# Connectors.net
KiCad netlist of a schematic drawn in Altium Designer
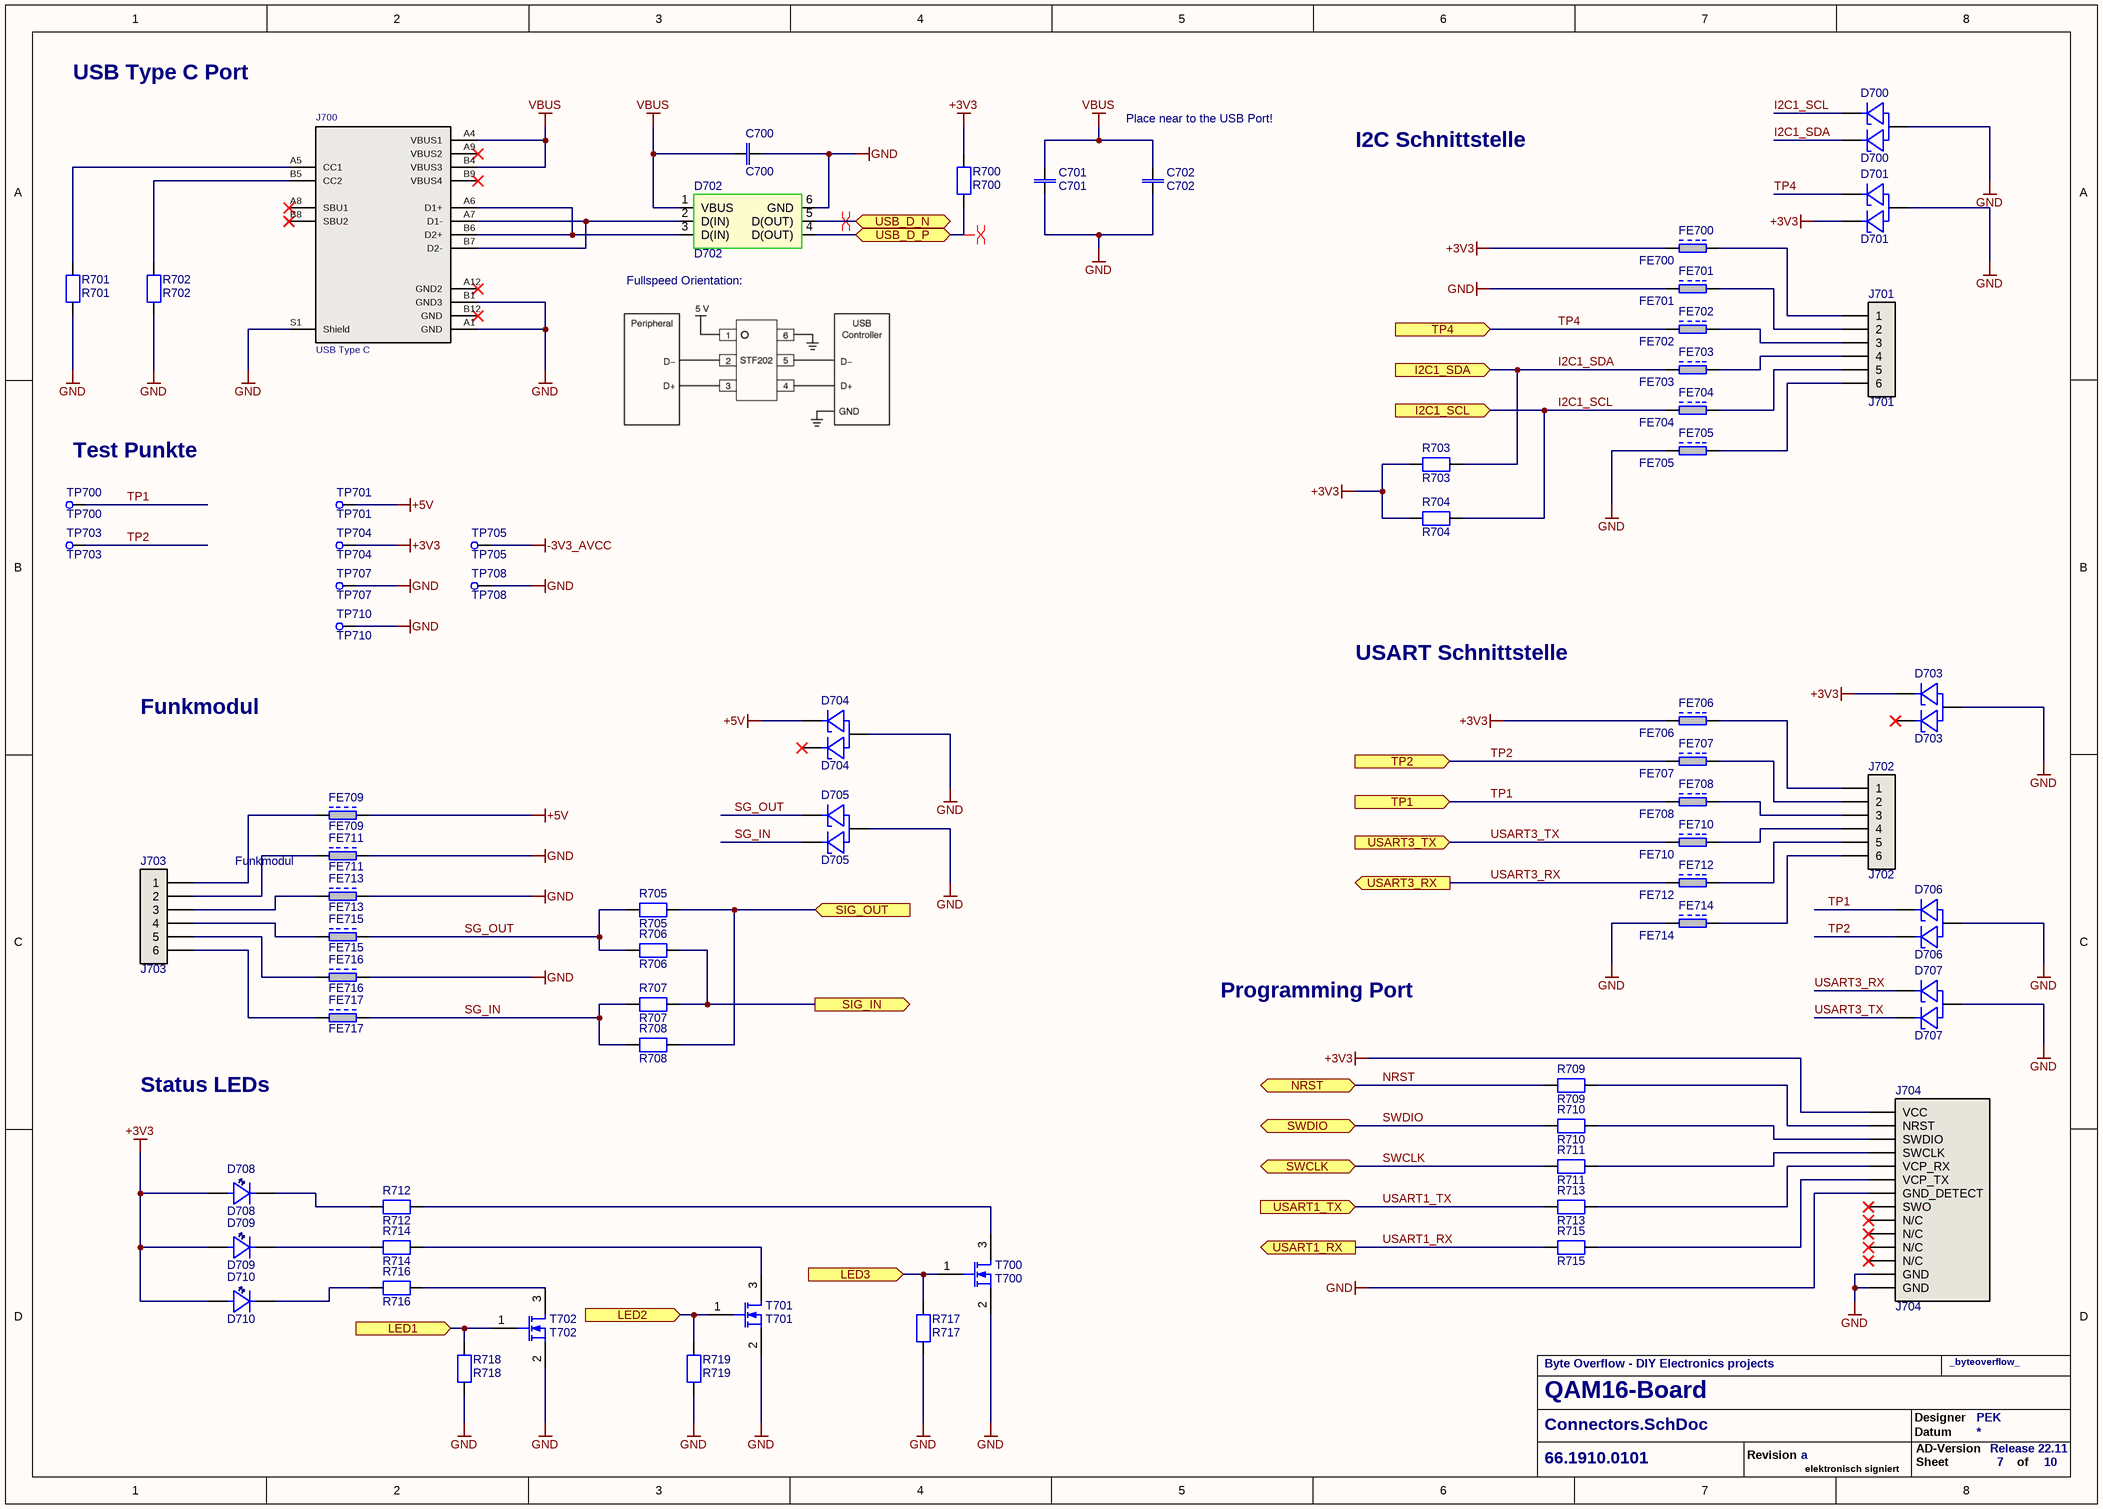
[diagram p0: Connectors.SchDoc]

(export (version "E")
  (design (tool "Eeschema 10.0.6"))
  (components
    (comp (ref "C700")
      (value "C 1uF 50V")
      (footprint "0805-2012")
      (description "Capacitor")
      (fields
        (field (name "MANUFACTURER") "Murata Electronics North America")
        (field (name "MANUFACTURER PART NUMBER") "GRM21BF51H105ZA12L")
      )
      (libsource (lib "Database_Libs1") (part "Kondensator"))
    )
    (comp (ref "C701")
      (value "C 1uF 50V")
      (footprint "0805-2012")
      (description "Capacitor")
      (fields
        (field (name "MANUFACTURER") "Murata Electronics North America")
        (field (name "MANUFACTURER PART NUMBER") "GRM21BF51H105ZA12L")
      )
      (libsource (lib "Database_Libs1") (part "Kondensator"))
    )
    (comp (ref "C702")
      (value "C 1uF 50V")
      (footprint "0805-2012")
      (description "Capacitor")
      (fields
        (field (name "MANUFACTURER") "Murata Electronics North America")
        (field (name "MANUFACTURER PART NUMBER") "GRM21BF51H105ZA12L")
      )
      (libsource (lib "Database_Libs1") (part "Kondensator"))
    )
    (comp (ref "D700")
      (value "PESD5V2S2UT 215")
      (footprint "SOT-23-3")
      (description "Diode")
      (fields
        (field (name "MANUFACTURER") "Nexperia USA Inc.")
        (field (name "MANUFACTURER PART NUMBER") "PESD5V2S2UT,215")
      )
      (libsource (lib "Database_Libs1") (part "PESD5V2S2UT"))
    )
    (comp (ref "D701")
      (value "PESD5V2S2UT 215")
      (footprint "SOT-23-3")
      (description "Diode")
      (fields
        (field (name "MANUFACTURER") "Nexperia USA Inc.")
        (field (name "MANUFACTURER PART NUMBER") "PESD5V2S2UT,215")
      )
      (libsource (lib "Database_Libs1") (part "PESD5V2S2UT"))
    )
    (comp (ref "D702")
      (value "STF202-22T1G")
      (footprint "SOT-23-6")
      (description "Diode")
      (fields (field (name "MANUFACTURER") "ON Semiconductor"))
      (libsource (lib "Database_Libs1") (part "STF202-22T1G"))
    )
    (comp (ref "D703")
      (value "PESD5V2S2UT 215")
      (footprint "SOT-23-3")
      (description "Diode")
      (fields
        (field (name "MANUFACTURER") "Nexperia USA Inc.")
        (field (name "MANUFACTURER PART NUMBER") "PESD5V2S2UT,215")
      )
      (libsource (lib "Database_Libs1") (part "PESD5V2S2UT"))
    )
    (comp (ref "D704")
      (value "PESD5V2S2UT 215")
      (footprint "SOT-23-3")
      (description "Diode")
      (fields
        (field (name "MANUFACTURER") "Nexperia USA Inc.")
        (field (name "MANUFACTURER PART NUMBER") "PESD5V2S2UT,215")
      )
      (libsource (lib "Database_Libs1") (part "PESD5V2S2UT"))
    )
    (comp (ref "D705")
      (value "PESD5V2S2UT 215")
      (footprint "SOT-23-3")
      (description "Diode")
      (fields
        (field (name "MANUFACTURER") "Nexperia USA Inc.")
        (field (name "MANUFACTURER PART NUMBER") "PESD5V2S2UT,215")
      )
      (libsource (lib "Database_Libs1") (part "PESD5V2S2UT"))
    )
    (comp (ref "D706")
      (value "PESD5V2S2UT 215")
      (footprint "SOT-23-3")
      (description "Diode")
      (fields
        (field (name "MANUFACTURER") "Nexperia USA Inc.")
        (field (name "MANUFACTURER PART NUMBER") "PESD5V2S2UT,215")
      )
      (libsource (lib "Database_Libs1") (part "PESD5V2S2UT"))
    )
    (comp (ref "D707")
      (value "PESD5V2S2UT 215")
      (footprint "SOT-23-3")
      (description "Diode")
      (fields
        (field (name "MANUFACTURER") "Nexperia USA Inc.")
        (field (name "MANUFACTURER PART NUMBER") "PESD5V2S2UT,215")
      )
      (libsource (lib "Database_Libs1") (part "PESD5V2S2UT"))
    )
    (comp (ref "D708")
      (value "LED SMD 0805")
      (footprint "0805_LED")
      (description "LED")
      (fields
        (field (name "MANUFACTURER") "Dialight")
        (field (name "MANUFACTURER PART NUMBER") "5988170107F")
        (field (name "VERIFICATION") "25.01.2013 MLP")
      )
      (libsource (lib "Database_Libs1") (part "LED"))
    )
    (comp (ref "D709")
      (value "LED SMD 0805")
      (footprint "0805_LED")
      (description "LED")
      (fields
        (field (name "MANUFACTURER") "Dialight")
        (field (name "MANUFACTURER PART NUMBER") "5988170107F")
        (field (name "VERIFICATION") "25.01.2013 MLP")
      )
      (libsource (lib "Database_Libs1") (part "LED"))
    )
    (comp (ref "D710")
      (value "LED SMD 0805")
      (footprint "0805_LED")
      (description "LED")
      (fields
        (field (name "MANUFACTURER") "Dialight")
        (field (name "MANUFACTURER PART NUMBER") "5988170107F")
        (field (name "VERIFICATION") "25.01.2013 MLP")
      )
      (libsource (lib "Database_Libs1") (part "LED"))
    )
    (comp (ref "FE700")
      (value "BLM18AG102SN1D")
      (footprint "0603-1608")
      (description "Ferrite")
      (fields (field (name "MANUFACTURER") "Murata Electronics North America"))
      (libsource (lib "Database_Libs1") (part "Ferrit"))
    )
    (comp (ref "FE701")
      (value "BLM18AG102SN1D")
      (footprint "0603-1608")
      (description "Ferrite")
      (fields (field (name "MANUFACTURER") "Murata Electronics North America"))
      (libsource (lib "Database_Libs1") (part "Ferrit"))
    )
    (comp (ref "FE702")
      (value "BLM18AG102SN1D")
      (footprint "0603-1608")
      (description "Ferrite")
      (fields (field (name "MANUFACTURER") "Murata Electronics North America"))
      (libsource (lib "Database_Libs1") (part "Ferrit"))
    )
    (comp (ref "FE703")
      (value "BLM18AG102SN1D")
      (footprint "0603-1608")
      (description "Ferrite")
      (fields (field (name "MANUFACTURER") "Murata Electronics North America"))
      (libsource (lib "Database_Libs1") (part "Ferrit"))
    )
    (comp (ref "FE704")
      (value "BLM18AG102SN1D")
      (footprint "0603-1608")
      (description "Ferrite")
      (fields (field (name "MANUFACTURER") "Murata Electronics North America"))
      (libsource (lib "Database_Libs1") (part "Ferrit"))
    )
    (comp (ref "FE705")
      (value "BLM18AG102SN1D")
      (footprint "0603-1608")
      (description "Ferrite")
      (fields (field (name "MANUFACTURER") "Murata Electronics North America"))
      (libsource (lib "Database_Libs1") (part "Ferrit"))
    )
    (comp (ref "FE706")
      (value "BLM18AG102SN1D")
      (footprint "0603-1608")
      (description "Ferrite")
      (fields (field (name "MANUFACTURER") "Murata Electronics North America"))
      (libsource (lib "Database_Libs1") (part "Ferrit"))
    )
    (comp (ref "FE707")
      (value "BLM18AG102SN1D")
      (footprint "0603-1608")
      (description "Ferrite")
      (fields (field (name "MANUFACTURER") "Murata Electronics North America"))
      (libsource (lib "Database_Libs1") (part "Ferrit"))
    )
    (comp (ref "FE708")
      (value "BLM18AG102SN1D")
      (footprint "0603-1608")
      (description "Ferrite")
      (fields (field (name "MANUFACTURER") "Murata Electronics North America"))
      (libsource (lib "Database_Libs1") (part "Ferrit"))
    )
    (comp (ref "FE709")
      (value "BLM18AG102SN1D")
      (footprint "0603-1608")
      (description "Ferrite")
      (fields (field (name "MANUFACTURER") "Murata Electronics North America"))
      (libsource (lib "Database_Libs1") (part "Ferrit"))
    )
    (comp (ref "FE710")
      (value "BLM18AG102SN1D")
      (footprint "0603-1608")
      (description "Ferrite")
      (fields (field (name "MANUFACTURER") "Murata Electronics North America"))
      (libsource (lib "Database_Libs1") (part "Ferrit"))
    )
    (comp (ref "FE711")
      (value "BLM18AG102SN1D")
      (footprint "0603-1608")
      (description "Ferrite")
      (fields (field (name "MANUFACTURER") "Murata Electronics North America"))
      (libsource (lib "Database_Libs1") (part "Ferrit"))
    )
    (comp (ref "FE712")
      (value "BLM18AG102SN1D")
      (footprint "0603-1608")
      (description "Ferrite")
      (fields (field (name "MANUFACTURER") "Murata Electronics North America"))
      (libsource (lib "Database_Libs1") (part "Ferrit"))
    )
    (comp (ref "FE713")
      (value "BLM18AG102SN1D")
      (footprint "0603-1608")
      (description "Ferrite")
      (fields (field (name "MANUFACTURER") "Murata Electronics North America"))
      (libsource (lib "Database_Libs1") (part "Ferrit"))
    )
    (comp (ref "FE714")
      (value "BLM18AG102SN1D")
      (footprint "0603-1608")
      (description "Ferrite")
      (fields (field (name "MANUFACTURER") "Murata Electronics North America"))
      (libsource (lib "Database_Libs1") (part "Ferrit"))
    )
    (comp (ref "FE715")
      (value "BLM18AG102SN1D")
      (footprint "0603-1608")
      (description "Ferrite")
      (fields (field (name "MANUFACTURER") "Murata Electronics North America"))
      (libsource (lib "Database_Libs1") (part "Ferrit"))
    )
    (comp (ref "FE716")
      (value "BLM18AG102SN1D")
      (footprint "0603-1608")
      (description "Ferrite")
      (fields (field (name "MANUFACTURER") "Murata Electronics North America"))
      (libsource (lib "Database_Libs1") (part "Ferrit"))
    )
    (comp (ref "FE717")
      (value "BLM18AG102SN1D")
      (footprint "0603-1608")
      (description "Ferrite")
      (fields (field (name "MANUFACTURER") "Murata Electronics North America"))
      (libsource (lib "Database_Libs1") (part "Ferrit"))
    )
    (comp (ref "J700")
      (value "USB Type C")
      (footprint "GCT_USB4105")
      (description "Connector")
      (fields (field (name "MP") "1054500101") (field (name "MF") "Molex"))
      (libsource (lib "Database_Libs1") (part "USB 2.0 Type C"))
    )
    (comp (ref "J701")
      (value "Stiftleiste 6pol")
      (footprint "Stiftleiste_6pol")
      (description "Connector")
      (libsource (lib "Database_Libs1") (part "Stiftleiste_6pol"))
    )
    (comp (ref "J702")
      (value "Stiftleiste 6pol")
      (footprint "Stiftleiste_6pol")
      (description "Connector")
      (libsource (lib "Database_Libs1") (part "Stiftleiste_6pol"))
    )
    (comp (ref "J703")
      (value "Stiftleiste 6pol")
      (footprint "Stiftleiste_6pol")
      (description "Connector")
      (libsource (lib "") (part "Stiftleiste_6pol_1"))
    )
    (comp (ref "J704")
      (value "Stiftleiste_Stlink_V3")
      (footprint "SAMTEC_FTSH-107-01-L-DV-K-A")
      (description "Connector")
      (fields
        (field (name "MANUFACTURER") "Samtec")
        (field (name "MANUFACTURER PART NUMBER") "FTSH-107-01-L-DV-K-A")
      )
      (libsource (lib "Database_Libs1") (part "Stiftleiste_Stlink_V3"))
    )
    (comp (ref "R700")
      (value "R 1.5k 1%")
      (footprint "0603-1608")
      (description "Resistor")
      (fields
        (field (name "MANUFACTURER") "Vishay Dale")
        (field (name "MANUFACTURER PART NUMBER") "CRCW06031K50FKEA")
        (field (name "VERIFICATION") "05.07.2012 OPT")
      )
      (libsource (lib "Database_Libs1") (part "Resistor"))
    )
    (comp (ref "R701")
      (value "R 5.1k 1%")
      (footprint "0603-1608")
      (description "Resistor")
      (fields
        (field (name "MANUFACTURER") "Vishay Dale")
        (field (name "MANUFACTURER PART NUMBER") "CRCW06035K10FKEA")
        (field (name "VERIFICATION") "05.07.2012 OPT")
      )
      (libsource (lib "Database_Libs1") (part "Resistor"))
    )
    (comp (ref "R702")
      (value "R 5.1k 1%")
      (footprint "0603-1608")
      (description "Resistor")
      (fields
        (field (name "MANUFACTURER") "Vishay Dale")
        (field (name "MANUFACTURER PART NUMBER") "CRCW06035K10FKEA")
        (field (name "VERIFICATION") "05.07.2012 OPT")
      )
      (libsource (lib "Database_Libs1") (part "Resistor"))
    )
    (comp (ref "R703")
      (value "R 2.2k 1%")
      (footprint "0603-1608")
      (description "Resistor")
      (fields
        (field (name "MANUFACTURER") "Vishay Dale")
        (field (name "MANUFACTURER PART NUMBER") "CRCW06032K20FKEA")
        (field (name "VERIFICATION") "05.07.2012 OPT")
      )
      (libsource (lib "Database_Libs1") (part "Resistor"))
    )
    (comp (ref "R704")
      (value "R 2.2k 1%")
      (footprint "0603-1608")
      (description "Resistor")
      (fields
        (field (name "MANUFACTURER") "Vishay Dale")
        (field (name "MANUFACTURER PART NUMBER") "CRCW06032K20FKEA")
        (field (name "VERIFICATION") "05.07.2012 OPT")
      )
      (libsource (lib "Database_Libs1") (part "Resistor"))
    )
    (comp (ref "R705")
      (value "R 0E 1%")
      (footprint "0805-2012")
      (description "Resistor")
      (fields
        (field (name "MANUFACTURER") "Vishay Dale")
        (field (name "MANUFACTURER PART NUMBER") "CRCW08050000Z0EAHP")
        (field (name "VERIFICATION") "05.03.2013 ENP")
      )
      (libsource (lib "Database_Libs1") (part "Resistor"))
    )
    (comp (ref "R706")
      (value "R 0E 1%")
      (footprint "0805-2012")
      (description "Resistor")
      (fields
        (field (name "MANUFACTURER") "Vishay Dale")
        (field (name "MANUFACTURER PART NUMBER") "CRCW08050000Z0EAHP")
        (field (name "VERIFICATION") "05.03.2013 ENP")
      )
      (libsource (lib "Database_Libs1") (part "Resistor"))
    )
    (comp (ref "R707")
      (value "R 0E 1%")
      (footprint "0805-2012")
      (description "Resistor")
      (fields
        (field (name "MANUFACTURER") "Vishay Dale")
        (field (name "MANUFACTURER PART NUMBER") "CRCW08050000Z0EAHP")
        (field (name "VERIFICATION") "05.03.2013 ENP")
      )
      (libsource (lib "Database_Libs1") (part "Resistor"))
    )
    (comp (ref "R708")
      (value "R 0E 1%")
      (footprint "0805-2012")
      (description "Resistor")
      (fields
        (field (name "MANUFACTURER") "Vishay Dale")
        (field (name "MANUFACTURER PART NUMBER") "CRCW08050000Z0EAHP")
        (field (name "VERIFICATION") "05.03.2013 ENP")
      )
      (libsource (lib "Database_Libs1") (part "Resistor"))
    )
    (comp (ref "R709")
      (value "R 100E 1%")
      (footprint "0603-1608")
      (description "Resistor")
      (fields
        (field (name "MANUFACTURER") "Vishay Dale")
        (field (name "MANUFACTURER PART NUMBER") "CRCW0603100RFKEA")
        (field (name "VERIFICATION") "05.07.2012 OPT")
      )
      (libsource (lib "Database_Libs1") (part "Resistor"))
    )
    (comp (ref "R710")
      (value "R 100E 1%")
      (footprint "0603-1608")
      (description "Resistor")
      (fields
        (field (name "MANUFACTURER") "Vishay Dale")
        (field (name "MANUFACTURER PART NUMBER") "CRCW0603100RFKEA")
        (field (name "VERIFICATION") "05.07.2012 OPT")
      )
      (libsource (lib "Database_Libs1") (part "Resistor"))
    )
    (comp (ref "R711")
      (value "R 100E 1%")
      (footprint "0603-1608")
      (description "Resistor")
      (fields
        (field (name "MANUFACTURER") "Vishay Dale")
        (field (name "MANUFACTURER PART NUMBER") "CRCW0603100RFKEA")
        (field (name "VERIFICATION") "05.07.2012 OPT")
      )
      (libsource (lib "Database_Libs1") (part "Resistor"))
    )
    (comp (ref "R712")
      (value "R 560E 1%")
      (footprint "0805-2012")
      (description "Resistor")
      (fields
        (field (name "MANUFACTURER") "Panasonic Electronic Components")
        (field (name "MANUFACTURER PART NUMBER") "ERJ-6ENF5600V")
      )
      (libsource (lib "Database_Libs1") (part "Resistor"))
    )
    (comp (ref "R713")
      (value "R 100E 1%")
      (footprint "0603-1608")
      (description "Resistor")
      (fields
        (field (name "MANUFACTURER") "Vishay Dale")
        (field (name "MANUFACTURER PART NUMBER") "CRCW0603100RFKEA")
        (field (name "VERIFICATION") "05.07.2012 OPT")
      )
      (libsource (lib "Database_Libs1") (part "Resistor"))
    )
    (comp (ref "R714")
      (value "R 560E 1%")
      (footprint "0805-2012")
      (description "Resistor")
      (fields
        (field (name "MANUFACTURER") "Panasonic Electronic Components")
        (field (name "MANUFACTURER PART NUMBER") "ERJ-6ENF5600V")
      )
      (libsource (lib "Database_Libs1") (part "Resistor"))
    )
    (comp (ref "R715")
      (value "R 100E 1%")
      (footprint "0603-1608")
      (description "Resistor")
      (fields
        (field (name "MANUFACTURER") "Vishay Dale")
        (field (name "MANUFACTURER PART NUMBER") "CRCW0603100RFKEA")
        (field (name "VERIFICATION") "05.07.2012 OPT")
      )
      (libsource (lib "Database_Libs1") (part "Resistor"))
    )
    (comp (ref "R716")
      (value "R 560E 1%")
      (footprint "0805-2012")
      (description "Resistor")
      (fields
        (field (name "MANUFACTURER") "Panasonic Electronic Components")
        (field (name "MANUFACTURER PART NUMBER") "ERJ-6ENF5600V")
      )
      (libsource (lib "Database_Libs1") (part "Resistor"))
    )
    (comp (ref "R717")
      (value "R 100k 1%")
      (footprint "0603-1608")
      (description "Resistor")
      (fields
        (field (name "MANUFACTURER") "Vishay Dale")
        (field (name "MANUFACTURER PART NUMBER") "CRCW0603100KFKEA")
        (field (name "VERIFICATION") "05.07.2012 OPT")
      )
      (libsource (lib "Database_Libs1") (part "Resistor"))
    )
    (comp (ref "R718")
      (value "R 100k 1%")
      (footprint "0603-1608")
      (description "Resistor")
      (fields
        (field (name "MANUFACTURER") "Vishay Dale")
        (field (name "MANUFACTURER PART NUMBER") "CRCW0603100KFKEA")
        (field (name "VERIFICATION") "05.07.2012 OPT")
      )
      (libsource (lib "Database_Libs1") (part "Resistor"))
    )
    (comp (ref "R719")
      (value "R 100k 1%")
      (footprint "0603-1608")
      (description "Resistor")
      (fields
        (field (name "MANUFACTURER") "Vishay Dale")
        (field (name "MANUFACTURER PART NUMBER") "CRCW0603100KFKEA")
        (field (name "VERIFICATION") "05.07.2012 OPT")
      )
      (libsource (lib "Database_Libs1") (part "Resistor"))
    )
    (comp (ref "T700")
      (value "SI1308EDL-T1-GE3")
      (footprint "SOT-323")
      (description "FET")
      (fields (field (name "MANUFACTURER") "Vishay Siliconix"))
      (libsource (lib "Database_Libs1") (part "FDV305N"))
    )
    (comp (ref "T701")
      (value "SI1308EDL-T1-GE3")
      (footprint "SOT-323")
      (description "FET")
      (fields (field (name "MANUFACTURER") "Vishay Siliconix"))
      (libsource (lib "Database_Libs1") (part "FDV305N"))
    )
    (comp (ref "T702")
      (value "SI1308EDL-T1-GE3")
      (footprint "SOT-323")
      (description "FET")
      (fields (field (name "MANUFACTURER") "Vishay Siliconix"))
      (libsource (lib "Database_Libs1") (part "FDV305N"))
    )
    (comp (ref "TP700")
      (value "Testpoint")
      (footprint "Testpoint")
      (fields
        (field (name "MANUFACTURER") "Keystone Electronics")
        (field (name "MANUFACTURER PART NUMBER") "5006")
      )
      (libsource (lib "Database_Libs1") (part "Testpoint"))
    )
    (comp (ref "TP701")
      (value "Testpoint")
      (footprint "Testpoint")
      (fields
        (field (name "MANUFACTURER") "Keystone Electronics")
        (field (name "MANUFACTURER PART NUMBER") "5006")
      )
      (libsource (lib "Database_Libs1") (part "Testpoint"))
    )
    (comp (ref "TP703")
      (value "Testpoint")
      (footprint "Testpoint")
      (fields
        (field (name "MANUFACTURER") "Keystone Electronics")
        (field (name "MANUFACTURER PART NUMBER") "5006")
      )
      (libsource (lib "Database_Libs1") (part "Testpoint"))
    )
    (comp (ref "TP704")
      (value "Testpoint")
      (footprint "Testpoint")
      (fields
        (field (name "MANUFACTURER") "Keystone Electronics")
        (field (name "MANUFACTURER PART NUMBER") "5006")
      )
      (libsource (lib "Database_Libs1") (part "Testpoint"))
    )
    (comp (ref "TP705")
      (value "Testpoint")
      (footprint "Testpoint")
      (fields
        (field (name "MANUFACTURER") "Keystone Electronics")
        (field (name "MANUFACTURER PART NUMBER") "5006")
      )
      (libsource (lib "Database_Libs1") (part "Testpoint"))
    )
    (comp (ref "TP707")
      (value "Testpoint")
      (footprint "Testpoint")
      (fields
        (field (name "MANUFACTURER") "Keystone Electronics")
        (field (name "MANUFACTURER PART NUMBER") "5006")
      )
      (libsource (lib "Database_Libs1") (part "Testpoint"))
    )
    (comp (ref "TP708")
      (value "Testpoint")
      (footprint "Testpoint")
      (fields
        (field (name "MANUFACTURER") "Keystone Electronics")
        (field (name "MANUFACTURER PART NUMBER") "5006")
      )
      (libsource (lib "Database_Libs1") (part "Testpoint"))
    )
    (comp (ref "TP710")
      (value "Testpoint")
      (footprint "Testpoint")
      (fields
        (field (name "MANUFACTURER") "Keystone Electronics")
        (field (name "MANUFACTURER PART NUMBER") "5006")
      )
      (libsource (lib "Database_Libs1") (part "Testpoint"))
    )
  )
  (nets
    (net (code "1") (name "+3V3") (class "Default")
      (node (ref "D701") (pin "1") (pinfunction "1_1") (pintype "passive"))
      (node (ref "D703") (pin "2") (pinfunction "2_2") (pintype "passive"))
      (node (ref "D708") (pin "1") (pinfunction "A_1") (pintype "passive"))
      (node (ref "D709") (pin "1") (pinfunction "A_1") (pintype "passive"))
      (node (ref "D710") (pin "1") (pinfunction "A_1") (pintype "passive"))
      (node (ref "FE700") (pin "1") (pintype "passive"))
      (node (ref "FE706") (pin "1") (pintype "passive"))
      (node (ref "J704") (pin "3") (pinfunction "VCC_3") (pintype "passive"))
      (node (ref "R700") (pin "1") (pinfunction "1_1") (pintype "passive"))
      (node (ref "R703") (pin "1") (pinfunction "1_1") (pintype "passive"))
      (node (ref "R704") (pin "1") (pinfunction "1_1") (pintype "passive"))
      (node (ref "TP704") (pin "1") (pintype "passive"))
    )
    (net (code "2") (name "+5V") (class "Default")
      (node (ref "D704") (pin "2") (pinfunction "2_2") (pintype "passive"))
      (node (ref "FE709") (pin "1") (pintype "passive"))
      (node (ref "TP701") (pin "1") (pintype "passive"))
    )
    (net (code "3") (name "-3V3_AVCC") (class "Default") (node (ref "TP705") (pin "1") (pintype "passive")))
    (net (code "4") (name "/I2C1_SCL") (class "Default")
      (node (ref "D700") (pin "2") (pinfunction "2_2") (pintype "passive"))
      (node (ref "FE704") (pin "1") (pintype "passive"))
      (node (ref "R704") (pin "2") (pinfunction "2_2") (pintype "passive"))
    )
    (net (code "5") (name "/I2C1_SDA") (class "Default")
      (node (ref "D700") (pin "1") (pinfunction "1_1") (pintype "passive"))
      (node (ref "FE703") (pin "1") (pintype "passive"))
      (node (ref "R703") (pin "2") (pinfunction "2_2") (pintype "passive"))
    )
    (net (code "6") (name "/LED1") (class "Default")
      (node (ref "R718") (pin "1") (pinfunction "1_1") (pintype "passive"))
      (node (ref "T702") (pin "1") (pinfunction "G_1") (pintype "passive"))
    )
    (net (code "7") (name "/LED2") (class "Default")
      (node (ref "R719") (pin "1") (pinfunction "1_1") (pintype "passive"))
      (node (ref "T701") (pin "1") (pinfunction "G_1") (pintype "passive"))
    )
    (net (code "8") (name "/LED3") (class "Default")
      (node (ref "R717") (pin "1") (pinfunction "1_1") (pintype "passive"))
      (node (ref "T700") (pin "1") (pinfunction "G_1") (pintype "passive"))
    )
    (net (code "9") (name "/NRST") (class "Default")
      (node (ref "R709") (pin "1") (pinfunction "1_1") (pintype "passive"))
    )
    (net (code "10") (name "/SG_IN") (class "Default")
      (node (ref "D705") (pin "1") (pinfunction "1_1") (pintype "passive"))
      (node (ref "FE717") (pin "1") (pintype "passive"))
      (node (ref "R707") (pin "1") (pinfunction "1_1") (pintype "passive"))
      (node (ref "R708") (pin "1") (pinfunction "1_1") (pintype "passive"))
    )
    (net (code "11") (name "/SG_OUT") (class "Default")
      (node (ref "D705") (pin "2") (pinfunction "2_2") (pintype "passive"))
      (node (ref "FE715") (pin "1") (pintype "passive"))
      (node (ref "R705") (pin "1") (pinfunction "1_1") (pintype "passive"))
      (node (ref "R706") (pin "1") (pinfunction "1_1") (pintype "passive"))
    )
    (net (code "12") (name "/SIG_IN") (class "Default")
      (node (ref "R706") (pin "2") (pinfunction "2_2") (pintype "passive"))
      (node (ref "R707") (pin "2") (pinfunction "2_2") (pintype "passive"))
    )
    (net (code "13") (name "/SIG_OUT") (class "Default")
      (node (ref "R705") (pin "2") (pinfunction "2_2") (pintype "passive"))
      (node (ref "R708") (pin "2") (pinfunction "2_2") (pintype "passive"))
    )
    (net (code "14") (name "/SWCLK") (class "Default")
      (node (ref "R711") (pin "1") (pinfunction "1_1") (pintype "passive"))
    )
    (net (code "15") (name "/SWDIO") (class "Default")
      (node (ref "R710") (pin "1") (pinfunction "1_1") (pintype "passive"))
    )
    (net (code "16") (name "/TP1") (class "Default")
      (node (ref "D706") (pin "2") (pinfunction "2_2") (pintype "passive"))
      (node (ref "FE708") (pin "1") (pintype "passive"))
      (node (ref "TP700") (pin "1") (pintype "passive"))
    )
    (net (code "17") (name "/TP2") (class "Default")
      (node (ref "D706") (pin "1") (pinfunction "1_1") (pintype "passive"))
      (node (ref "FE707") (pin "1") (pintype "passive"))
      (node (ref "TP703") (pin "1") (pintype "passive"))
    )
    (net (code "18") (name "/TP4") (class "Default")
      (node (ref "D701") (pin "2") (pinfunction "2_2") (pintype "passive"))
      (node (ref "FE702") (pin "1") (pintype "passive"))
    )
    (net (code "19") (name "/USART1_RX") (class "Default")
      (node (ref "R715") (pin "1") (pinfunction "1_1") (pintype "passive"))
    )
    (net (code "20") (name "/USART1_TX") (class "Default")
      (node (ref "R713") (pin "1") (pinfunction "1_1") (pintype "passive"))
    )
    (net (code "21") (name "/USART3_RX") (class "Default")
      (node (ref "D707") (pin "2") (pinfunction "2_2") (pintype "passive"))
      (node (ref "FE712") (pin "1") (pintype "passive"))
    )
    (net (code "22") (name "/USART3_TX") (class "Default")
      (node (ref "D707") (pin "1") (pinfunction "1_1") (pintype "passive"))
      (node (ref "FE710") (pin "1") (pintype "passive"))
    )
    (net (code "23") (name "/USB_D_N") (class "Default")
      (node (ref "D702") (pin "5") (pinfunction "D(OUT)_5") (pintype "passive"))
    )
    (net (code "24") (name "/USB_D_P") (class "Default")
      (node (ref "D702") (pin "4") (pinfunction "D(OUT)_4") (pintype "passive"))
      (node (ref "R700") (pin "2") (pinfunction "2_2") (pintype "passive"))
    )
    (net (code "25") (name "GND") (class "Default")
      (node (ref "C700") (pin "2") (pinfunction "2_2") (pintype "passive"))
      (node (ref "C701") (pin "2") (pinfunction "2_2") (pintype "passive"))
      (node (ref "C702") (pin "2") (pinfunction "2_2") (pintype "passive"))
      (node (ref "D700") (pin "3") (pinfunction "3_3") (pintype "passive"))
      (node (ref "D701") (pin "3") (pinfunction "3_3") (pintype "passive"))
      (node (ref "D702") (pin "6") (pinfunction "GND_6") (pintype "passive"))
      (node (ref "D703") (pin "3") (pinfunction "3_3") (pintype "passive"))
      (node (ref "D704") (pin "3") (pinfunction "3_3") (pintype "passive"))
      (node (ref "D705") (pin "3") (pinfunction "3_3") (pintype "passive"))
      (node (ref "D706") (pin "3") (pinfunction "3_3") (pintype "passive"))
      (node (ref "D707") (pin "3") (pinfunction "3_3") (pintype "passive"))
      (node (ref "FE701") (pin "1") (pintype "passive"))
      (node (ref "FE705") (pin "1") (pintype "passive"))
      (node (ref "FE711") (pin "1") (pintype "passive"))
      (node (ref "FE713") (pin "1") (pintype "passive"))
      (node (ref "FE714") (pin "1") (pintype "passive"))
      (node (ref "FE716") (pin "1") (pintype "passive"))
      (node (ref "J700") (pin "A1") (pinfunction "GND_A1") (pintype "passive"))
      (node (ref "J700") (pin "B1") (pinfunction "GND3_B1") (pintype "passive"))
      (node (ref "J700") (pin "S1") (pinfunction "Shield_S1") (pintype "passive"))
      (node (ref "J704") (pin "11") (pinfunction "GND_DETECT_11") (pintype "passive"))
      (node (ref "J704") (pin "5") (pinfunction "GND_5") (pintype "passive"))
      (node (ref "J704") (pin "7") (pinfunction "GND_7") (pintype "passive"))
      (node (ref "R701") (pin "2") (pinfunction "2_2") (pintype "passive"))
      (node (ref "R702") (pin "2") (pinfunction "2_2") (pintype "passive"))
      (node (ref "R717") (pin "2") (pinfunction "2_2") (pintype "passive"))
      (node (ref "R718") (pin "2") (pinfunction "2_2") (pintype "passive"))
      (node (ref "R719") (pin "2") (pinfunction "2_2") (pintype "passive"))
      (node (ref "T700") (pin "2") (pinfunction "S_2") (pintype "passive"))
      (node (ref "T701") (pin "2") (pinfunction "S_2") (pintype "passive"))
      (node (ref "T702") (pin "2") (pinfunction "S_2") (pintype "passive"))
      (node (ref "TP707") (pin "1") (pintype "passive"))
      (node (ref "TP708") (pin "1") (pintype "passive"))
      (node (ref "TP710") (pin "1") (pintype "passive"))
    )
    (net (code "26") (name "Net-(D708-K)") (class "Default")
      (node (ref "D708") (pin "2") (pinfunction "K_2") (pintype "passive"))
      (node (ref "R712") (pin "1") (pinfunction "1_1") (pintype "passive"))
    )
    (net (code "27") (name "Net-(D709-K)") (class "Default")
      (node (ref "D709") (pin "2") (pinfunction "K_2") (pintype "passive"))
      (node (ref "R714") (pin "1") (pinfunction "1_1") (pintype "passive"))
    )
    (net (code "28") (name "Net-(D710-K)") (class "Default")
      (node (ref "D710") (pin "2") (pinfunction "K_2") (pintype "passive"))
      (node (ref "R716") (pin "1") (pinfunction "1_1") (pintype "passive"))
    )
    (net (code "29") (name "Net-(FE700-Pad2)") (class "Default")
      (node (ref "FE700") (pin "2") (pintype "passive"))
      (node (ref "J701") (pin "1") (pinfunction "1_1") (pintype "passive"))
    )
    (net (code "30") (name "Net-(FE701-Pad2)") (class "Default")
      (node (ref "FE701") (pin "2") (pintype "passive"))
      (node (ref "J701") (pin "2") (pinfunction "2_2") (pintype "passive"))
    )
    (net (code "31") (name "Net-(FE702-Pad2)") (class "Default")
      (node (ref "FE702") (pin "2") (pintype "passive"))
      (node (ref "J701") (pin "3") (pinfunction "3_3") (pintype "passive"))
    )
    (net (code "32") (name "Net-(FE703-Pad2)") (class "Default")
      (node (ref "FE703") (pin "2") (pintype "passive"))
      (node (ref "J701") (pin "4") (pinfunction "4_4") (pintype "passive"))
    )
    (net (code "33") (name "Net-(FE704-Pad2)") (class "Default")
      (node (ref "FE704") (pin "2") (pintype "passive"))
      (node (ref "J701") (pin "5") (pinfunction "5_5") (pintype "passive"))
    )
    (net (code "34") (name "Net-(FE705-Pad2)") (class "Default")
      (node (ref "FE705") (pin "2") (pintype "passive"))
      (node (ref "J701") (pin "6") (pinfunction "6_6") (pintype "passive"))
    )
    (net (code "35") (name "Net-(FE706-Pad2)") (class "Default")
      (node (ref "FE706") (pin "2") (pintype "passive"))
      (node (ref "J702") (pin "1") (pinfunction "1_1") (pintype "passive"))
    )
    (net (code "36") (name "Net-(FE707-Pad2)") (class "Default")
      (node (ref "FE707") (pin "2") (pintype "passive"))
      (node (ref "J702") (pin "2") (pinfunction "2_2") (pintype "passive"))
    )
    (net (code "37") (name "Net-(FE708-Pad2)") (class "Default")
      (node (ref "FE708") (pin "2") (pintype "passive"))
      (node (ref "J702") (pin "3") (pinfunction "3_3") (pintype "passive"))
    )
    (net (code "38") (name "Net-(FE709-Pad2)") (class "Default")
      (node (ref "FE709") (pin "2") (pintype "passive"))
      (node (ref "J703") (pin "1") (pinfunction "1_1") (pintype "passive"))
    )
    (net (code "39") (name "Net-(FE710-Pad2)") (class "Default")
      (node (ref "FE710") (pin "2") (pintype "passive"))
      (node (ref "J702") (pin "4") (pinfunction "4_4") (pintype "passive"))
    )
    (net (code "40") (name "Net-(FE711-Pad2)") (class "Default")
      (node (ref "FE711") (pin "2") (pintype "passive"))
      (node (ref "J703") (pin "2") (pinfunction "2_2") (pintype "passive"))
    )
    (net (code "41") (name "Net-(FE712-Pad2)") (class "Default")
      (node (ref "FE712") (pin "2") (pintype "passive"))
      (node (ref "J702") (pin "5") (pinfunction "5_5") (pintype "passive"))
    )
    (net (code "42") (name "Net-(FE713-Pad2)") (class "Default")
      (node (ref "FE713") (pin "2") (pintype "passive"))
      (node (ref "J703") (pin "3") (pinfunction "3_3") (pintype "passive"))
    )
    (net (code "43") (name "Net-(FE714-Pad2)") (class "Default")
      (node (ref "FE714") (pin "2") (pintype "passive"))
      (node (ref "J702") (pin "6") (pinfunction "6_6") (pintype "passive"))
    )
    (net (code "44") (name "Net-(FE715-Pad2)") (class "Default")
      (node (ref "FE715") (pin "2") (pintype "passive"))
      (node (ref "J703") (pin "4") (pinfunction "4_4") (pintype "passive"))
    )
    (net (code "45") (name "Net-(FE716-Pad2)") (class "Default")
      (node (ref "FE716") (pin "2") (pintype "passive"))
      (node (ref "J703") (pin "5") (pinfunction "5_5") (pintype "passive"))
    )
    (net (code "46") (name "Net-(FE717-Pad2)") (class "Default")
      (node (ref "FE717") (pin "2") (pintype "passive"))
      (node (ref "J703") (pin "6") (pinfunction "6_6") (pintype "passive"))
    )
    (net (code "47") (name "Net-(J700-CC1)") (class "Default")
      (node (ref "J700") (pin "A5") (pinfunction "CC1_A5") (pintype "passive"))
      (node (ref "R701") (pin "1") (pinfunction "1_1") (pintype "passive"))
    )
    (net (code "48") (name "Net-(J700-CC2)") (class "Default")
      (node (ref "J700") (pin "B5") (pinfunction "CC2_B5") (pintype "passive"))
      (node (ref "R702") (pin "1") (pinfunction "1_1") (pintype "passive"))
    )
    (net (code "49") (name "Net-(J700-D1+)") (class "Default")
      (node (ref "D702") (pin "3") (pinfunction "D(IN)_3") (pintype "passive"))
      (node (ref "J700") (pin "A6") (pinfunction "D1+_A6") (pintype "passive"))
      (node (ref "J700") (pin "B6") (pinfunction "D2+_B6") (pintype "passive"))
    )
    (net (code "50") (name "Net-(J700-D1-)") (class "Default")
      (node (ref "D702") (pin "2") (pinfunction "D(IN)_2") (pintype "passive"))
      (node (ref "J700") (pin "A7") (pinfunction "D1-_A7") (pintype "passive"))
      (node (ref "J700") (pin "B7") (pinfunction "D2-_B7") (pintype "passive"))
    )
    (net (code "51") (name "Net-(J704-NRST)") (class "Default")
      (node (ref "J704") (pin "12") (pinfunction "NRST_12") (pintype "passive"))
      (node (ref "R709") (pin "2") (pinfunction "2_2") (pintype "passive"))
    )
    (net (code "52") (name "Net-(J704-SWCLK)") (class "Default")
      (node (ref "J704") (pin "6") (pinfunction "SWCLK_6") (pintype "passive"))
      (node (ref "R711") (pin "2") (pinfunction "2_2") (pintype "passive"))
    )
    (net (code "53") (name "Net-(J704-SWDIO)") (class "Default")
      (node (ref "J704") (pin "4") (pinfunction "SWDIO_4") (pintype "passive"))
      (node (ref "R710") (pin "2") (pinfunction "2_2") (pintype "passive"))
    )
    (net (code "54") (name "Net-(J704-VCP_RX)") (class "Default")
      (node (ref "J704") (pin "13") (pinfunction "VCP_RX_13") (pintype "passive"))
      (node (ref "R713") (pin "2") (pinfunction "2_2") (pintype "passive"))
    )
    (net (code "55") (name "Net-(J704-VCP_TX)") (class "Default")
      (node (ref "J704") (pin "14") (pinfunction "VCP_TX_14") (pintype "passive"))
      (node (ref "R715") (pin "2") (pinfunction "2_2") (pintype "passive"))
    )
    (net (code "56") (name "Net-(T700-D)") (class "Default")
      (node (ref "R712") (pin "2") (pinfunction "2_2") (pintype "passive"))
      (node (ref "T700") (pin "3") (pinfunction "D_3") (pintype "passive"))
    )
    (net (code "57") (name "Net-(T701-D)") (class "Default")
      (node (ref "R714") (pin "2") (pinfunction "2_2") (pintype "passive"))
      (node (ref "T701") (pin "3") (pinfunction "D_3") (pintype "passive"))
    )
    (net (code "58") (name "Net-(T702-D)") (class "Default")
      (node (ref "R716") (pin "2") (pinfunction "2_2") (pintype "passive"))
      (node (ref "T702") (pin "3") (pinfunction "D_3") (pintype "passive"))
    )
    (net (code "59") (name "VBUS") (class "Default")
      (node (ref "C700") (pin "1") (pinfunction "1_1") (pintype "passive"))
      (node (ref "C701") (pin "1") (pinfunction "1_1") (pintype "passive"))
      (node (ref "C702") (pin "1") (pinfunction "1_1") (pintype "passive"))
      (node (ref "D702") (pin "1") (pinfunction "VBUS_1") (pintype "passive"))
      (node (ref "J700") (pin "A4") (pinfunction "VBUS1_A4") (pintype "passive"))
      (node (ref "J700") (pin "B4") (pinfunction "VBUS3_B4") (pintype "passive"))
    )
    (net (code "60") (name "unconnected-(D703-Pad1)") (class "Default")
      (node (ref "D703") (pin "1") (pinfunction "1_1") (pintype "passive+no_connect"))
    )
    (net (code "61") (name "unconnected-(D704-Pad1)") (class "Default")
      (node (ref "D704") (pin "1") (pinfunction "1_1") (pintype "passive+no_connect"))
    )
    (net (code "62") (name "unconnected-(J700-GND-PadB12)") (class "Default")
      (node (ref "J700") (pin "B12") (pinfunction "GND_B12") (pintype "passive+no_connect"))
    )
    (net (code "63") (name "unconnected-(J700-GND2-PadA12)") (class "Default")
      (node (ref "J700") (pin "A12") (pinfunction "GND2_A12") (pintype "passive+no_connect"))
    )
    (net (code "64") (name "unconnected-(J700-SBU1-PadA8)") (class "Default")
      (node (ref "J700") (pin "A8") (pinfunction "SBU1_A8") (pintype "passive+no_connect"))
    )
    (net (code "65") (name "unconnected-(J700-SBU2-PadB8)") (class "Default")
      (node (ref "J700") (pin "B8") (pinfunction "SBU2_B8") (pintype "passive+no_connect"))
    )
    (net (code "66") (name "unconnected-(J700-VBUS2-PadA9)") (class "Default")
      (node (ref "J700") (pin "A9") (pinfunction "VBUS2_A9") (pintype "passive+no_connect"))
    )
    (net (code "67") (name "unconnected-(J700-VBUS4-PadB9)") (class "Default")
      (node (ref "J700") (pin "B9") (pinfunction "VBUS4_B9") (pintype "passive+no_connect"))
    )
    (net (code "68") (name "unconnected-(J704-N{slash}C-Pad1)") (class "Default")
      (node (ref "J704") (pin "1") (pinfunction "N/C_1") (pintype "passive+no_connect"))
    )
    (net (code "69") (name "unconnected-(J704-N{slash}C-Pad2)") (class "Default")
      (node (ref "J704") (pin "2") (pinfunction "N/C_2") (pintype "passive+no_connect"))
    )
    (net (code "70") (name "unconnected-(J704-N{slash}C-Pad9)") (class "Default")
      (node (ref "J704") (pin "9") (pinfunction "N/C_9") (pintype "passive+no_connect"))
    )
    (net (code "71") (name "unconnected-(J704-N{slash}C-Pad10)") (class "Default")
      (node (ref "J704") (pin "10") (pinfunction "N/C_10") (pintype "passive+no_connect"))
    )
    (net (code "72") (name "unconnected-(J704-SWO-Pad8)") (class "Default")
      (node (ref "J704") (pin "8") (pinfunction "SWO_8") (pintype "passive+no_connect"))
    )
  )
)
